# band-single-feather.net
KiCad netlist of a schematic drawn in EAGLE
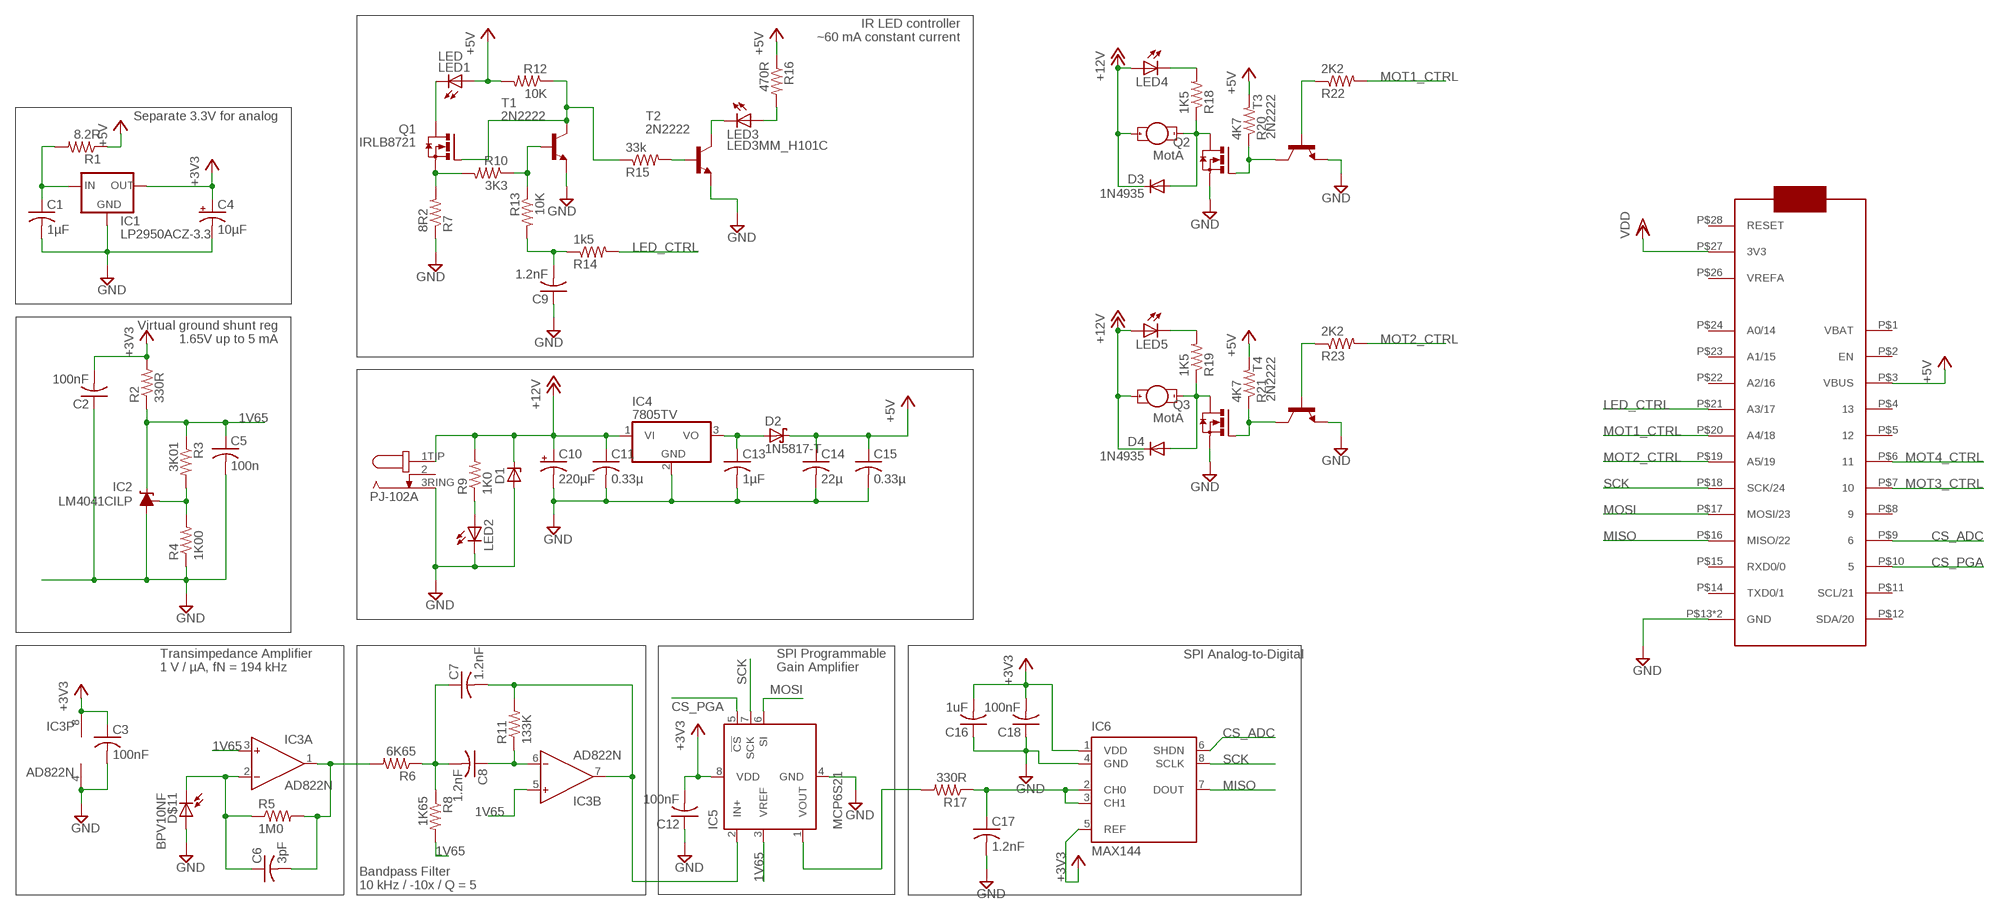
[diagram p0: schematic, sheet 1]

(export (version "E")
  (design (tool "Eeschema 10.0.6"))
  (components
    (comp (ref "C1")
      (value "1µF")
      (footprint "eagle-import:C025-030X050")
      (fields (field (name "MANF") "TDK Corporation"))
      (libsource (lib "eagle-import") (part "C-US025-030X050"))
    )
    (comp (ref "C2")
      (value "100nF")
      (footprint "eagle-import:C025-025X050")
      (fields (field (name "MANF") "Vishay BC Components"))
      (libsource (lib "eagle-import") (part "C-US025-025X050"))
    )
    (comp (ref "C3")
      (value "100nF")
      (footprint "eagle-import:C025-025X050")
      (fields (field (name "MANF") "Vishay BC Components"))
      (libsource (lib "eagle-import") (part "C-US025-025X050"))
    )
    (comp (ref "C4")
      (value "10µF")
      (footprint "eagle-import:E2,5-5")
      (fields (field (name "MANF") "AVX Corporation"))
      (libsource (lib "eagle-import") (part "CPOL-USE2.5-5"))
    )
    (comp (ref "C5")
      (value "100n")
      (footprint "eagle-import:C025-025X050")
      (fields (field (name "MANF") "Vishay BC Components"))
      (libsource (lib "eagle-import") (part "C-US025-025X050"))
    )
    (comp (ref "C6")
      (value "3pF")
      (footprint "eagle-import:C025-024X044")
      (fields (field (name "MANF") "TDK Corporation"))
      (libsource (lib "eagle-import") (part "C-US025-024X044"))
    )
    (comp (ref "C7")
      (value "1.2nF")
      (footprint "eagle-import:C025-025X050")
      (fields (field (name "MANF") "Vishay BC Components"))
      (libsource (lib "eagle-import") (part "C-US025-025X050"))
    )
    (comp (ref "C8")
      (value "1.2nF")
      (footprint "eagle-import:C025-025X050")
      (fields (field (name "MANF") "Vishay BC Components"))
      (libsource (lib "eagle-import") (part "C-US025-025X050"))
    )
    (comp (ref "C9")
      (value "1.2nF")
      (footprint "eagle-import:C025-025X050")
      (fields (field (name "MANF") "Vishay BC Components"))
      (libsource (lib "eagle-import") (part "C-US025-025X050"))
    )
    (comp (ref "C10")
      (value "220µF")
      (footprint "eagle-import:E3,5-8")
      (fields (field (name "MANF") "Panasonic Electronic Components"))
      (libsource (lib "eagle-import") (part "CPOL-USE3.5-8"))
    )
    (comp (ref "C11")
      (value "0.33µ")
      (footprint "eagle-import:C025-050X050")
      (fields (field (name "MANF") "TDK Corporation"))
      (libsource (lib "eagle-import") (part "C-US025-050X050"))
    )
    (comp (ref "C12")
      (value "100nF")
      (footprint "eagle-import:C025-025X050")
      (fields (field (name "MANF") "Vishay BC Components"))
      (libsource (lib "eagle-import") (part "C-US025-025X050"))
    )
    (comp (ref "C13")
      (value "1µF")
      (footprint "eagle-import:C025-030X050")
      (fields (field (name "MANF") "TDK Corporation"))
      (libsource (lib "eagle-import") (part "C-US025-030X050"))
    )
    (comp (ref "C14")
      (value "22µ")
      (footprint "eagle-import:C050-045X075")
      (fields (field (name "MANF") "TDK Corporation"))
      (libsource (lib "eagle-import") (part "C-US050-045X075"))
    )
    (comp (ref "C15")
      (value "0.33µ")
      (footprint "eagle-import:C025-050X050")
      (fields (field (name "MANF") "TDK Corporation"))
      (libsource (lib "eagle-import") (part "C-US025-050X050"))
    )
    (comp (ref "C16")
      (value "1uF")
      (footprint "eagle-import:C025-025X050")
      (fields (field (name "MANF") "TDK Corporation"))
      (libsource (lib "eagle-import") (part "C-US025-025X050"))
    )
    (comp (ref "C17")
      (value "1.2nF")
      (footprint "eagle-import:C025-025X050")
      (fields (field (name "MANF") "Vishay BC Components"))
      (libsource (lib "eagle-import") (part "C-US025-025X050"))
    )
    (comp (ref "C18")
      (value "100nF")
      (footprint "eagle-import:C025-025X050")
      (fields (field (name "MANF") "Vishay BC Components"))
      (libsource (lib "eagle-import") (part "C-US025-025X050"))
    )
    (comp (ref "D$11")
      (value "BPV10NF")
      (footprint "eagle-import:LED5MM")
      (fields (field (name "MANF") "Vishay Semiconductor Opto Division"))
      (libsource (lib "eagle-import") (part "BPV10NF"))
    )
    (comp (ref "D1")
      (value "ZENER-DIODEF126-10")
      (footprint "eagle-import:F126Z10")
      (fields (field (name "MANF") "Littelfuse Inc."))
      (libsource (lib "eagle-import") (part "ZENER-DIODEF126-10"))
    )
    (comp (ref "D2")
      (value "1N5817-T")
      (footprint "eagle-import:DO41-7.6")
      (fields (field (name "MANF") "Fairchild Semiconductor"))
      (libsource (lib "eagle-import") (part "1N5817-T"))
    )
    (comp (ref "D3")
      (value "1N4935")
      (footprint "eagle-import:DO41-10")
      (fields (field (name "MANF") "Fairchild Semiconductor"))
      (libsource (lib "eagle-import") (part "1N4004"))
    )
    (comp (ref "D4")
      (value "1N4935")
      (footprint "eagle-import:DO41-10")
      (fields (field (name "MANF") "Fairchild Semiconductor"))
      (libsource (lib "eagle-import") (part "1N4004"))
    )
    (comp (ref "IC1")
      (value "LP2950ACZ-3.3")
      (footprint "eagle-import:TO92")
      (fields (field (name "MANF") "Texas Instruments"))
      (libsource (lib "eagle-import") (part "LP2950?ACZ-3.3"))
    )
    (comp (ref "IC2")
      (value "LM4041CILP")
      (footprint "eagle-import:LP_O-PBCY-W3")
      (fields (field (name "MANF") "Texas Instruments"))
      (libsource (lib "eagle-import") (part "LM4041ILPC"))
    )
    (comp (ref "IC3")
      (value "AD822N")
      (footprint "eagle-import:DIL08")
      (fields
        (field (name "MANF") "Analog Devices Inc.")
        (field (name "DIGIKEY#") "AD823ANZ-ND")
        (field (name "MANF#") "AD823ANZ")
      )
      (libsource (lib "eagle-import") (part "AD822N"))
    )
    (comp (ref "IC4")
      (value "7805TV")
      (footprint "eagle-import:TO220V")
      (fields (field (name "MANF") "Fairchild Semiconductor"))
      (libsource (lib "eagle-import") (part "78TV05"))
    )
    (comp (ref "IC5")
      (value "MCP6S21")
      (footprint "eagle-import:DIL08")
      (fields (field (name "MANF") "Microchip Technology"))
      (libsource (lib "eagle-import") (part "MCP6S21"))
    )
    (comp (ref "IC6")
      (value "MAX144")
      (footprint "eagle-import:DIL08")
      (fields (field (name "MANF") "Maxim Integrated"))
      (libsource (lib "eagle-import") (part "MAX144"))
    )
    (comp (ref "IC7")
      (value "FEATHER_M0")
      (footprint "eagle-import:FEATHER_M0")
      (fields (field (name "MANF") "Adafruit Industries LLC"))
      (libsource (lib "eagle-import") (part "FEATHER_M0"))
    )
    (comp (ref "J1")
      (value "PJ-102A")
      (footprint "eagle-import:PJ-102A")
      (fields (field (name "MANF") "CUI Inc."))
      (libsource (lib "eagle-import") (part "PJ-102A"))
    )
    (comp (ref "J2")
      (value "MotA")
      (footprint "eagle-import:1X02_3.5MM_MOT")
      (fields (field (name "MANF") "On Shore Technology Inc."))
      (libsource (lib "eagle-import") (part "1X02_3.5MM_MOT"))
    )
    (comp (ref "J3")
      (value "MotA")
      (footprint "eagle-import:1X02_3.5MM_MOT")
      (fields (field (name "MANF") "On Shore Technology Inc."))
      (libsource (lib "eagle-import") (part "1X02_3.5MM_MOT"))
    )
    (comp (ref "LED1")
      (value "LED")
      (footprint "eagle-import:1X02_3.5MM")
      (fields (field (name "MANF") "OSRAM Opto Semiconductors Inc"))
      (libsource (lib "eagle-import") (part "1X02_3.5MM_LED"))
    )
    (comp (ref "LED2")
      (value "LED5MM")
      (footprint "eagle-import:LED5MM")
      (fields (field (name "MANF") "Kingbright"))
      (libsource (lib "eagle-import") (part "LED5MM"))
    )
    (comp (ref "LED3")
      (value "LED3MM_H101C")
      (footprint "eagle-import:LED3MM_H101C")
      (fields (field (name "MANF") "Kingbright"))
      (libsource (lib "eagle-import") (part "LED3MM_H101C"))
    )
    (comp (ref "LED4")
      (value "LED3MM")
      (footprint "eagle-import:LED3MM")
      (fields (field (name "MANF") "Kingbright"))
      (libsource (lib "eagle-import") (part "LED3MM"))
    )
    (comp (ref "LED5")
      (value "LED3MM")
      (footprint "eagle-import:LED3MM")
      (fields (field (name "MANF") "Kingbright"))
      (libsource (lib "eagle-import") (part "LED3MM"))
    )
    (comp (ref "Q1")
      (value "IRLB8721")
      (footprint "eagle-import:TO220BV")
      (fields (field (name "MANF") "Infineon Technologies"))
      (libsource (lib "eagle-import") (part "IRLB8721"))
    )
    (comp (ref "Q2")
      (value "IRLB8721")
      (footprint "eagle-import:TO220BV")
      (fields (field (name "MANF") "International Rectifier"))
      (libsource (lib "eagle-import") (part "IRLB8721"))
    )
    (comp (ref "Q3")
      (value "IRLB8721")
      (footprint "eagle-import:TO220BV")
      (fields (field (name "MANF") "International Rectifier"))
      (libsource (lib "eagle-import") (part "IRLB8721"))
    )
    (comp (ref "R1")
      (value "8.2R")
      (footprint "eagle-import:0207_9")
      (fields (field (name "MANF") "Stackpole Electronics Inc."))
      (libsource (lib "eagle-import") (part "R-US_0207/9"))
    )
    (comp (ref "R2")
      (value "330R")
      (footprint "eagle-import:0207_9")
      (fields (field (name "MANF") "Stackpole Electronics Inc."))
      (libsource (lib "eagle-import") (part "R-US_0207/9"))
    )
    (comp (ref "R3")
      (value "3K01")
      (footprint "eagle-import:0207_9")
      (fields (field (name "MANF") "Stackpole Electronics Inc."))
      (libsource (lib "eagle-import") (part "R-US_0207/9"))
    )
    (comp (ref "R4")
      (value "1K00")
      (footprint "eagle-import:0207_9")
      (fields (field (name "MANF") "Stackpole Electronics Inc."))
      (libsource (lib "eagle-import") (part "R-US_0207/9"))
    )
    (comp (ref "R5")
      (value "1M0")
      (footprint "eagle-import:0207_9")
      (fields (field (name "MANF") "Stackpole Electronics Inc"))
      (libsource (lib "eagle-import") (part "R-US_0207/9"))
    )
    (comp (ref "R6")
      (value "6K65")
      (footprint "eagle-import:0207_9")
      (fields (field (name "MANF") "Yageo"))
      (libsource (lib "eagle-import") (part "R-US_0207/9"))
    )
    (comp (ref "R7")
      (value "8R2")
      (footprint "eagle-import:0207_9")
      (fields (field (name "DIGIKEY#") "S8.2HCT-ND") (field (name "MANF") "Stackpole Electronics Inc."))
      (libsource (lib "eagle-import") (part "R-US_0207/9"))
    )
    (comp (ref "R8")
      (value "1K65")
      (footprint "eagle-import:0207_9")
      (fields (field (name "MANF") "Yageo"))
      (libsource (lib "eagle-import") (part "R-US_0207/9"))
    )
    (comp (ref "R9")
      (value "1K0")
      (footprint "eagle-import:0207_9")
      (fields (field (name "MANF") "Stackpole Electronics Inc."))
      (libsource (lib "eagle-import") (part "R-US_0207/9"))
    )
    (comp (ref "R10")
      (value "3K3")
      (footprint "eagle-import:0207_9")
      (fields (field (name "MANF") "Stackpole Electronics Inc"))
      (libsource (lib "eagle-import") (part "R-US_0207/9"))
    )
    (comp (ref "R11")
      (value "133K")
      (footprint "eagle-import:0207_9")
      (fields (field (name "MANF") "Yageo"))
      (libsource (lib "eagle-import") (part "R-US_0207/9"))
    )
    (comp (ref "R12")
      (value "10K")
      (footprint "eagle-import:0207_9")
      (fields (field (name "MANF") "Stackpole Electronics Inc"))
      (libsource (lib "eagle-import") (part "R-US_0207/9"))
    )
    (comp (ref "R13")
      (value "10K")
      (footprint "eagle-import:0207_9")
      (fields (field (name "MANF") "Stackpole Electronics Inc"))
      (libsource (lib "eagle-import") (part "R-US_0207/9"))
    )
    (comp (ref "R14")
      (value "1k5")
      (footprint "eagle-import:0207_9")
      (fields (field (name "MANF") "Stackpole Electronics Inc"))
      (libsource (lib "eagle-import") (part "R-US_0207/9"))
    )
    (comp (ref "R15")
      (value "33k")
      (footprint "eagle-import:0207_9")
      (fields (field (name "MANF") "Stackpole Electronics Inc"))
      (libsource (lib "eagle-import") (part "R-US_0207/9"))
    )
    (comp (ref "R16")
      (value "470R")
      (footprint "eagle-import:0207_5V")
      (fields (field (name "MANF") "Stackpole Electronics Inc."))
      (libsource (lib "eagle-import") (part "R-US_0207/5V"))
    )
    (comp (ref "R17")
      (value "330R")
      (footprint "eagle-import:0207_9")
      (fields (field (name "MANF") "Stackpole Electronics Inc."))
      (libsource (lib "eagle-import") (part "R-US_0207/9"))
    )
    (comp (ref "R18")
      (value "1K5")
      (footprint "eagle-import:0207_10")
      (fields (field (name "MANF") "Stackpole Electronics Inc"))
      (libsource (lib "eagle-import") (part "R-US_0207/10"))
    )
    (comp (ref "R19")
      (value "1K5")
      (footprint "eagle-import:0207_10")
      (fields (field (name "MANF") "Stackpole Electronics Inc"))
      (libsource (lib "eagle-import") (part "R-US_0207/10"))
    )
    (comp (ref "R20")
      (value "4K7")
      (footprint "eagle-import:0207_10")
      (fields (field (name "MANF") "Stackpole Electronics Inc"))
      (libsource (lib "eagle-import") (part "R-US_0207/10"))
    )
    (comp (ref "R21")
      (value "4K7")
      (footprint "eagle-import:0207_10")
      (fields (field (name "MANF") "Stackpole Electronics Inc"))
      (libsource (lib "eagle-import") (part "R-US_0207/10"))
    )
    (comp (ref "R22")
      (value "2K2")
      (footprint "eagle-import:0207_10")
      (fields (field (name "MANF") "Stackpole Electronics Inc"))
      (libsource (lib "eagle-import") (part "R-US_0207/10"))
    )
    (comp (ref "R23")
      (value "2K2")
      (footprint "eagle-import:0207_10")
      (fields (field (name "MANF") "Stackpole Electronics Inc"))
      (libsource (lib "eagle-import") (part "R-US_0207/10"))
    )
    (comp (ref "T1")
      (value "2N2222")
      (footprint "eagle-import:TO92-EBC-OVAL")
      (fields (field (name "MANF") "Fairchild Semiconductor"))
      (libsource (lib "eagle-import") (part "2N2222"))
    )
    (comp (ref "T2")
      (value "2N2222")
      (footprint "eagle-import:TO92-EBC-OVAL")
      (fields (field (name "MANF") "Fairchild Semiconductor"))
      (libsource (lib "eagle-import") (part "2N2222"))
    )
    (comp (ref "T3")
      (value "2N2222")
      (footprint "eagle-import:TO92-EBC-OVAL")
      (fields (field (name "MANF") "Fairchild Semiconductor"))
      (libsource (lib "eagle-import") (part "2N2222"))
    )
    (comp (ref "T4")
      (value "2N2222")
      (footprint "eagle-import:TO92-EBC-OVAL")
      (fields (field (name "MANF") "Fairchild Semiconductor"))
      (libsource (lib "eagle-import") (part "2N2222"))
    )
  )
  (nets
    (net (code "1") (name "+3V3") (class "Default")
      (node (ref "C12") (pin "2") (pinfunction "2_2") (pintype "passive"))
      (node (ref "C16") (pin "2") (pinfunction "2_2") (pintype "passive"))
      (node (ref "C18") (pin "2") (pinfunction "2_2") (pintype "passive"))
      (node (ref "C2") (pin "2") (pinfunction "2_2") (pintype "passive"))
      (node (ref "C3") (pin "1") (pinfunction "1_1") (pintype "passive"))
      (node (ref "C4") (pin "+") (pinfunction "+_+") (pintype "passive"))
      (node (ref "IC1") (pin "1") (pinfunction "OUT_1") (pintype "passive"))
      (node (ref "IC3") (pin "8") (pinfunction "V+_8") (pintype "power_in"))
      (node (ref "IC5") (pin "8") (pinfunction "VDD_8") (pintype "power_in"))
      (node (ref "IC6") (pin "1") (pinfunction "VDD_1") (pintype "power_in"))
      (node (ref "IC6") (pin "5") (pinfunction "REF_5") (pintype "input"))
      (node (ref "R2") (pin "2") (pinfunction "2_2") (pintype "passive"))
    )
    (net (code "2") (name "+5V") (class "Default")
      (node (ref "C14") (pin "1") (pinfunction "1_1") (pintype "passive"))
      (node (ref "C15") (pin "1") (pinfunction "1_1") (pintype "passive"))
      (node (ref "D2") (pin "C") (pinfunction "C_C") (pintype "passive"))
      (node (ref "IC7") (pin "P$3") (pinfunction "VBUS_P$3") (pintype "bidirectional"))
      (node (ref "LED1") (pin "1A") (pinfunction "A_1A") (pintype "passive"))
      (node (ref "R1") (pin "1") (pinfunction "1_1") (pintype "passive"))
      (node (ref "R12") (pin "2") (pinfunction "2_2") (pintype "passive"))
      (node (ref "R16") (pin "1") (pinfunction "1_1") (pintype "passive"))
      (node (ref "R20") (pin "2") (pinfunction "2_2") (pintype "passive"))
      (node (ref "R21") (pin "2") (pinfunction "2_2") (pintype "passive"))
    )
    (net (code "3") (name "+12V") (class "Default")
      (node (ref "C10") (pin "+") (pinfunction "+_+") (pintype "passive"))
      (node (ref "C11") (pin "1") (pinfunction "1_1") (pintype "passive"))
      (node (ref "D1") (pin "C") (pinfunction "C_C") (pintype "passive"))
      (node (ref "D3") (pin "C") (pinfunction "C_C") (pintype "passive"))
      (node (ref "D4") (pin "C") (pinfunction "C_C") (pintype "passive"))
      (node (ref "IC4") (pin "1") (pinfunction "VI_1") (pintype "input"))
      (node (ref "J1") (pin "1TIP") (pinfunction "3TIP_1TIP") (pintype "passive"))
      (node (ref "J2") (pin "1A") (pinfunction "+_1A") (pintype "bidirectional"))
      (node (ref "J3") (pin "1A") (pinfunction "+_1A") (pintype "bidirectional"))
      (node (ref "LED4") (pin "A") (pinfunction "A_A") (pintype "passive"))
      (node (ref "LED5") (pin "A") (pinfunction "A_A") (pintype "passive"))
      (node (ref "R9") (pin "2") (pinfunction "2_2") (pintype "passive"))
    )
    (net (code "4") (name "/1V65") (class "Default")
      (node (ref "C5") (pin "1") (pinfunction "1_1") (pintype "passive"))
      (node (ref "IC2") (pin "2") (pinfunction "C_2") (pintype "passive"))
      (node (ref "IC3") (pin "3") (pinfunction "IN+_3") (pintype "input"))
      (node (ref "IC3") (pin "5") (pinfunction "IN+_5") (pintype "input"))
      (node (ref "IC5") (pin "3") (pinfunction "VREF_3") (pintype "input"))
      (node (ref "R2") (pin "1") (pinfunction "1_1") (pintype "passive"))
      (node (ref "R3") (pin "1") (pinfunction "1_1") (pintype "passive"))
      (node (ref "R8") (pin "2") (pinfunction "2_2") (pintype "passive"))
    )
    (net (code "5") (name "/CS_ADC") (class "Default")
      (node (ref "IC6") (pin "6") (pinfunction "SHDN_6") (pintype "input"))
      (node (ref "IC7") (pin "P$9") (pinfunction "6_P$9") (pintype "bidirectional"))
    )
    (net (code "6") (name "/CS_PGA") (class "Default")
      (node (ref "IC5") (pin "5") (pinfunction "~{CS}_5") (pintype "input"))
      (node (ref "IC7") (pin "P$10") (pinfunction "5_P$10") (pintype "bidirectional"))
    )
    (net (code "7") (name "/LED_CTRL") (class "Default")
      (node (ref "IC7") (pin "P$21") (pinfunction "A3/17_P$21") (pintype "bidirectional"))
      (node (ref "R14") (pin "2") (pinfunction "2_2") (pintype "passive"))
    )
    (net (code "8") (name "/MISO") (class "Default")
      (node (ref "IC6") (pin "7") (pinfunction "DOUT_7") (pintype "input"))
      (node (ref "IC7") (pin "P$16") (pinfunction "MISO/22_P$16") (pintype "bidirectional"))
    )
    (net (code "9") (name "/MOSI") (class "Default")
      (node (ref "IC5") (pin "6") (pinfunction "SI_6") (pintype "input"))
      (node (ref "IC7") (pin "P$17") (pinfunction "MOSI/23_P$17") (pintype "bidirectional"))
    )
    (net (code "10") (name "/MOT1_CTRL") (class "Default")
      (node (ref "IC7") (pin "P$20") (pinfunction "A4/18_P$20") (pintype "bidirectional"))
      (node (ref "R22") (pin "2") (pinfunction "2_2") (pintype "passive"))
    )
    (net (code "11") (name "/MOT2_CTRL") (class "Default")
      (node (ref "IC7") (pin "P$19") (pinfunction "A5/19_P$19") (pintype "bidirectional"))
      (node (ref "R23") (pin "2") (pinfunction "2_2") (pintype "passive"))
    )
    (net (code "12") (name "/MOT3_CTRL") (class "Default")
      (node (ref "IC7") (pin "P$7") (pinfunction "10_P$7") (pintype "bidirectional"))
    )
    (net (code "13") (name "/MOT4_CTRL") (class "Default")
      (node (ref "IC7") (pin "P$6") (pinfunction "11_P$6") (pintype "bidirectional"))
    )
    (net (code "14") (name "/SCK") (class "Default")
      (node (ref "IC5") (pin "7") (pinfunction "SCK_7") (pintype "input"))
      (node (ref "IC6") (pin "8") (pinfunction "SCLK_8") (pintype "input"))
      (node (ref "IC7") (pin "P$18") (pinfunction "SCK/24_P$18") (pintype "bidirectional"))
    )
    (net (code "15") (name "GND") (class "Default")
      (node (ref "C1") (pin "2") (pinfunction "2_2") (pintype "passive"))
      (node (ref "C10") (pin "-") (pinfunction "-_-") (pintype "passive"))
      (node (ref "C11") (pin "2") (pinfunction "2_2") (pintype "passive"))
      (node (ref "C12") (pin "1") (pinfunction "1_1") (pintype "passive"))
      (node (ref "C13") (pin "2") (pinfunction "2_2") (pintype "passive"))
      (node (ref "C14") (pin "2") (pinfunction "2_2") (pintype "passive"))
      (node (ref "C15") (pin "2") (pinfunction "2_2") (pintype "passive"))
      (node (ref "C16") (pin "1") (pinfunction "1_1") (pintype "passive"))
      (node (ref "C17") (pin "2") (pinfunction "2_2") (pintype "passive"))
      (node (ref "C18") (pin "1") (pinfunction "1_1") (pintype "passive"))
      (node (ref "C2") (pin "1") (pinfunction "1_1") (pintype "passive"))
      (node (ref "C3") (pin "2") (pinfunction "2_2") (pintype "passive"))
      (node (ref "C4") (pin "-") (pinfunction "-_-") (pintype "passive"))
      (node (ref "C5") (pin "2") (pinfunction "2_2") (pintype "passive"))
      (node (ref "C9") (pin "1") (pinfunction "1_1") (pintype "passive"))
      (node (ref "D$11") (pin "A") (pinfunction "A_A") (pintype "passive"))
      (node (ref "D1") (pin "A") (pinfunction "A_A") (pintype "passive"))
      (node (ref "IC1") (pin "2") (pinfunction "GND_2") (pintype "input"))
      (node (ref "IC2") (pin "3") (pinfunction "A_3") (pintype "passive"))
      (node (ref "IC3") (pin "4") (pinfunction "V-_4") (pintype "power_in"))
      (node (ref "IC4") (pin "2") (pinfunction "GND_2") (pintype "passive"))
      (node (ref "IC5") (pin "4") (pinfunction "GND_4") (pintype "power_in"))
      (node (ref "IC6") (pin "4") (pinfunction "GND_4") (pintype "power_in"))
      (node (ref "IC7") (pin "P$13") (pinfunction "GND_P$13") (pintype "bidirectional"))
      (node (ref "IC7") (pin "P$25") (pinfunction "GND_P$25") (pintype "bidirectional"))
      (node (ref "J1") (pin "3RING") (pinfunction "1RING_3RING") (pintype "passive"))
      (node (ref "LED2") (pin "K") (pinfunction "C_K") (pintype "passive"))
      (node (ref "Q2") (pin "S") (pinfunction "S_S") (pintype "passive"))
      (node (ref "Q3") (pin "S") (pinfunction "S_S") (pintype "passive"))
      (node (ref "R4") (pin "1") (pinfunction "1_1") (pintype "passive"))
      (node (ref "R7") (pin "1") (pinfunction "1_1") (pintype "passive"))
      (node (ref "T1") (pin "E") (pinfunction "E_E") (pintype "passive"))
      (node (ref "T2") (pin "E") (pinfunction "E_E") (pintype "passive"))
      (node (ref "T3") (pin "E") (pinfunction "E_E") (pintype "passive"))
      (node (ref "T4") (pin "E") (pinfunction "E_E") (pintype "passive"))
    )
    (net (code "16") (name "Net-(C7-Pad1)") (class "Default")
      (node (ref "C7") (pin "1") (pinfunction "1_1") (pintype "passive"))
      (node (ref "C8") (pin "2") (pinfunction "2_2") (pintype "passive"))
      (node (ref "R6") (pin "1") (pinfunction "1_1") (pintype "passive"))
      (node (ref "R8") (pin "1") (pinfunction "1_1") (pintype "passive"))
    )
    (net (code "17") (name "Net-(C9-Pad2)") (class "Default")
      (node (ref "C9") (pin "2") (pinfunction "2_2") (pintype "passive"))
      (node (ref "R13") (pin "2") (pinfunction "2_2") (pintype "passive"))
      (node (ref "R14") (pin "1") (pinfunction "1_1") (pintype "passive"))
    )
    (net (code "18") (name "Net-(IC1-IN)") (class "Default")
      (node (ref "C1") (pin "1") (pinfunction "1_1") (pintype "passive"))
      (node (ref "IC1") (pin "3") (pinfunction "IN_3") (pintype "input"))
      (node (ref "R1") (pin "2") (pinfunction "2_2") (pintype "passive"))
    )
    (net (code "19") (name "Net-(IC2-FB)") (class "Default")
      (node (ref "IC2") (pin "1") (pinfunction "FB_1") (pintype "passive"))
      (node (ref "R3") (pin "2") (pinfunction "2_2") (pintype "passive"))
      (node (ref "R4") (pin "2") (pinfunction "2_2") (pintype "passive"))
    )
    (net (code "20") (name "Net-(IC3A-IN-)") (class "Default")
      (node (ref "C6") (pin "1") (pinfunction "1_1") (pintype "passive"))
      (node (ref "D$11") (pin "K") (pinfunction "K_K") (pintype "passive"))
      (node (ref "IC3") (pin "2") (pinfunction "IN-_2") (pintype "input"))
      (node (ref "R5") (pin "1") (pinfunction "1_1") (pintype "passive"))
    )
    (net (code "21") (name "Net-(IC3A-OUT)") (class "Default")
      (node (ref "C6") (pin "2") (pinfunction "2_2") (pintype "passive"))
      (node (ref "IC3") (pin "1") (pinfunction "OUT_1") (pintype "output"))
      (node (ref "R5") (pin "2") (pinfunction "2_2") (pintype "passive"))
      (node (ref "R6") (pin "2") (pinfunction "2_2") (pintype "passive"))
    )
    (net (code "22") (name "Net-(IC3B-IN-)") (class "Default")
      (node (ref "C8") (pin "1") (pinfunction "1_1") (pintype "passive"))
      (node (ref "IC3") (pin "6") (pinfunction "IN-_6") (pintype "input"))
      (node (ref "R11") (pin "1") (pinfunction "1_1") (pintype "passive"))
    )
    (net (code "23") (name "Net-(IC3B-OUT)") (class "Default")
      (node (ref "C7") (pin "2") (pinfunction "2_2") (pintype "passive"))
      (node (ref "IC3") (pin "7") (pinfunction "OUT_7") (pintype "output"))
      (node (ref "IC5") (pin "2") (pinfunction "IN+_2") (pintype "input"))
      (node (ref "R11") (pin "2") (pinfunction "2_2") (pintype "passive"))
    )
    (net (code "24") (name "Net-(IC4-VO)") (class "Default")
      (node (ref "C13") (pin "1") (pinfunction "1_1") (pintype "passive"))
      (node (ref "D2") (pin "A") (pinfunction "A_A") (pintype "passive"))
      (node (ref "IC4") (pin "3") (pinfunction "VO_3") (pintype "passive"))
    )
    (net (code "25") (name "Net-(IC5-VOUT)") (class "Default")
      (node (ref "IC5") (pin "1") (pinfunction "VOUT_1") (pintype "output"))
      (node (ref "R17") (pin "2") (pinfunction "2_2") (pintype "passive"))
    )
    (net (code "26") (name "Net-(IC6-CH0)") (class "Default")
      (node (ref "C17") (pin "1") (pinfunction "1_1") (pintype "passive"))
      (node (ref "IC6") (pin "2") (pinfunction "CH0_2") (pintype "input"))
      (node (ref "IC6") (pin "3") (pinfunction "CH1_3") (pintype "input"))
      (node (ref "R17") (pin "1") (pinfunction "1_1") (pintype "passive"))
    )
    (net (code "27") (name "Net-(J2--)") (class "Default")
      (node (ref "D3") (pin "A") (pinfunction "A_A") (pintype "passive"))
      (node (ref "J2") (pin "2K") (pinfunction "-_2K") (pintype "bidirectional"))
      (node (ref "Q2") (pin "D") (pinfunction "D_D") (pintype "passive"))
      (node (ref "R18") (pin "1") (pinfunction "1_1") (pintype "passive"))
    )
    (net (code "28") (name "Net-(J3--)") (class "Default")
      (node (ref "D4") (pin "A") (pinfunction "A_A") (pintype "passive"))
      (node (ref "J3") (pin "2K") (pinfunction "-_2K") (pintype "bidirectional"))
      (node (ref "Q3") (pin "D") (pinfunction "D_D") (pintype "passive"))
      (node (ref "R19") (pin "1") (pinfunction "1_1") (pintype "passive"))
    )
    (net (code "29") (name "Net-(LED1-K)") (class "Default")
      (node (ref "LED1") (pin "2K") (pinfunction "K_2K") (pintype "passive"))
      (node (ref "Q1") (pin "D") (pinfunction "D_D") (pintype "passive"))
    )
    (net (code "30") (name "Net-(LED2-PadA)") (class "Default")
      (node (ref "LED2") (pin "A") (pinfunction "A_A") (pintype "passive"))
      (node (ref "R9") (pin "1") (pinfunction "1_1") (pintype "passive"))
    )
    (net (code "31") (name "Net-(LED3-PadA)") (class "Default")
      (node (ref "LED3") (pin "A") (pinfunction "A_A") (pintype "passive"))
      (node (ref "R16") (pin "2") (pinfunction "2_2") (pintype "passive"))
    )
    (net (code "32") (name "Net-(LED3-PadK)") (class "Default")
      (node (ref "LED3") (pin "K") (pinfunction "K_K") (pintype "passive"))
      (node (ref "T2") (pin "C") (pinfunction "C_C") (pintype "passive"))
    )
    (net (code "33") (name "Net-(LED4-C)") (class "Default")
      (node (ref "LED4") (pin "K") (pinfunction "C_K") (pintype "passive"))
      (node (ref "R18") (pin "2") (pinfunction "2_2") (pintype "passive"))
    )
    (net (code "34") (name "Net-(LED5-C)") (class "Default")
      (node (ref "LED5") (pin "K") (pinfunction "C_K") (pintype "passive"))
      (node (ref "R19") (pin "2") (pinfunction "2_2") (pintype "passive"))
    )
    (net (code "35") (name "Net-(Q1-PadG)") (class "Default")
      (node (ref "Q1") (pin "G") (pinfunction "G_G") (pintype "passive"))
      (node (ref "R12") (pin "1") (pinfunction "1_1") (pintype "passive"))
      (node (ref "R15") (pin "1") (pinfunction "1_1") (pintype "passive"))
      (node (ref "T1") (pin "C") (pinfunction "C_C") (pintype "passive"))
    )
    (net (code "36") (name "Net-(Q1-PadS)") (class "Default")
      (node (ref "Q1") (pin "S") (pinfunction "S_S") (pintype "passive"))
      (node (ref "R10") (pin "2") (pinfunction "2_2") (pintype "passive"))
      (node (ref "R7") (pin "2") (pinfunction "2_2") (pintype "passive"))
    )
    (net (code "37") (name "Net-(Q2-PadG)") (class "Default")
      (node (ref "Q2") (pin "G") (pinfunction "G_G") (pintype "passive"))
      (node (ref "R20") (pin "1") (pinfunction "1_1") (pintype "passive"))
      (node (ref "T3") (pin "C") (pinfunction "C_C") (pintype "passive"))
    )
    (net (code "38") (name "Net-(Q3-PadG)") (class "Default")
      (node (ref "Q3") (pin "G") (pinfunction "G_G") (pintype "passive"))
      (node (ref "R21") (pin "1") (pinfunction "1_1") (pintype "passive"))
      (node (ref "T4") (pin "C") (pinfunction "C_C") (pintype "passive"))
    )
    (net (code "39") (name "Net-(R10-Pad1)") (class "Default")
      (node (ref "R10") (pin "1") (pinfunction "1_1") (pintype "passive"))
      (node (ref "R13") (pin "1") (pinfunction "1_1") (pintype "passive"))
      (node (ref "T1") (pin "B") (pinfunction "B_B") (pintype "passive"))
    )
    (net (code "40") (name "Net-(R15-Pad2)") (class "Default")
      (node (ref "R15") (pin "2") (pinfunction "2_2") (pintype "passive"))
      (node (ref "T2") (pin "B") (pinfunction "B_B") (pintype "passive"))
    )
    (net (code "41") (name "Net-(R22-Pad1)") (class "Default")
      (node (ref "R22") (pin "1") (pinfunction "1_1") (pintype "passive"))
      (node (ref "T3") (pin "B") (pinfunction "B_B") (pintype "passive"))
    )
    (net (code "42") (name "Net-(R23-Pad1)") (class "Default")
      (node (ref "R23") (pin "1") (pinfunction "1_1") (pintype "passive"))
      (node (ref "T4") (pin "B") (pinfunction "B_B") (pintype "passive"))
    )
    (net (code "43") (name "VDD") (class "Default")
      (node (ref "IC7") (pin "P$27") (pinfunction "3V3_P$27") (pintype "bidirectional"))
    )
    (net (code "44") (name "unconnected-(IC7-9-PadP$8)") (class "Default")
      (node (ref "IC7") (pin "P$8") (pinfunction "9_P$8") (pintype "bidirectional"))
    )
    (net (code "45") (name "unconnected-(IC7-12-PadP$5)") (class "Default")
      (node (ref "IC7") (pin "P$5") (pinfunction "12_P$5") (pintype "bidirectional"))
    )
    (net (code "46") (name "unconnected-(IC7-13-PadP$4)") (class "Default")
      (node (ref "IC7") (pin "P$4") (pinfunction "13_P$4") (pintype "bidirectional"))
    )
    (net (code "47") (name "unconnected-(IC7-A0{slash}14-PadP$24)") (class "Default")
      (node (ref "IC7") (pin "P$24") (pinfunction "A0/14_P$24") (pintype "bidirectional"))
    )
    (net (code "48") (name "unconnected-(IC7-A1{slash}15-PadP$23)") (class "Default")
      (node (ref "IC7") (pin "P$23") (pinfunction "A1/15_P$23") (pintype "bidirectional"))
    )
    (net (code "49") (name "unconnected-(IC7-A2{slash}16-PadP$22)") (class "Default")
      (node (ref "IC7") (pin "P$22") (pinfunction "A2/16_P$22") (pintype "bidirectional"))
    )
    (net (code "50") (name "unconnected-(IC7-EN-PadP$2)") (class "Default")
      (node (ref "IC7") (pin "P$2") (pinfunction "EN_P$2") (pintype "bidirectional"))
    )
    (net (code "51") (name "unconnected-(IC7-RESET-PadP$28)") (class "Default")
      (node (ref "IC7") (pin "P$28") (pinfunction "RESET_P$28") (pintype "bidirectional"))
    )
    (net (code "52") (name "unconnected-(IC7-RXD0{slash}0-PadP$15)") (class "Default")
      (node (ref "IC7") (pin "P$15") (pinfunction "RXD0/0_P$15") (pintype "bidirectional"))
    )
    (net (code "53") (name "unconnected-(IC7-SCL{slash}21-PadP$11)") (class "Default")
      (node (ref "IC7") (pin "P$11") (pinfunction "SCL/21_P$11") (pintype "bidirectional"))
    )
    (net (code "54") (name "unconnected-(IC7-SDA{slash}20-PadP$12)") (class "Default")
      (node (ref "IC7") (pin "P$12") (pinfunction "SDA/20_P$12") (pintype "bidirectional"))
    )
    (net (code "55") (name "unconnected-(IC7-TXD0{slash}1-PadP$14)") (class "Default")
      (node (ref "IC7") (pin "P$14") (pinfunction "TXD0/1_P$14") (pintype "bidirectional"))
    )
    (net (code "56") (name "unconnected-(IC7-VBAT-PadP$1)") (class "Default")
      (node (ref "IC7") (pin "P$1") (pinfunction "VBAT_P$1") (pintype "bidirectional"))
    )
    (net (code "57") (name "unconnected-(IC7-VREFA-PadP$26)") (class "Default")
      (node (ref "IC7") (pin "P$26") (pinfunction "VREFA_P$26") (pintype "bidirectional"))
    )
    (net (code "58") (name "unconnected-(J1-Pad2)") (class "Default")
      (node (ref "J1") (pin "2") (pinfunction "2_2") (pintype "passive"))
    )
  )
)
